# Connector.net
KiCad netlist of a schematic drawn in Altium Designer
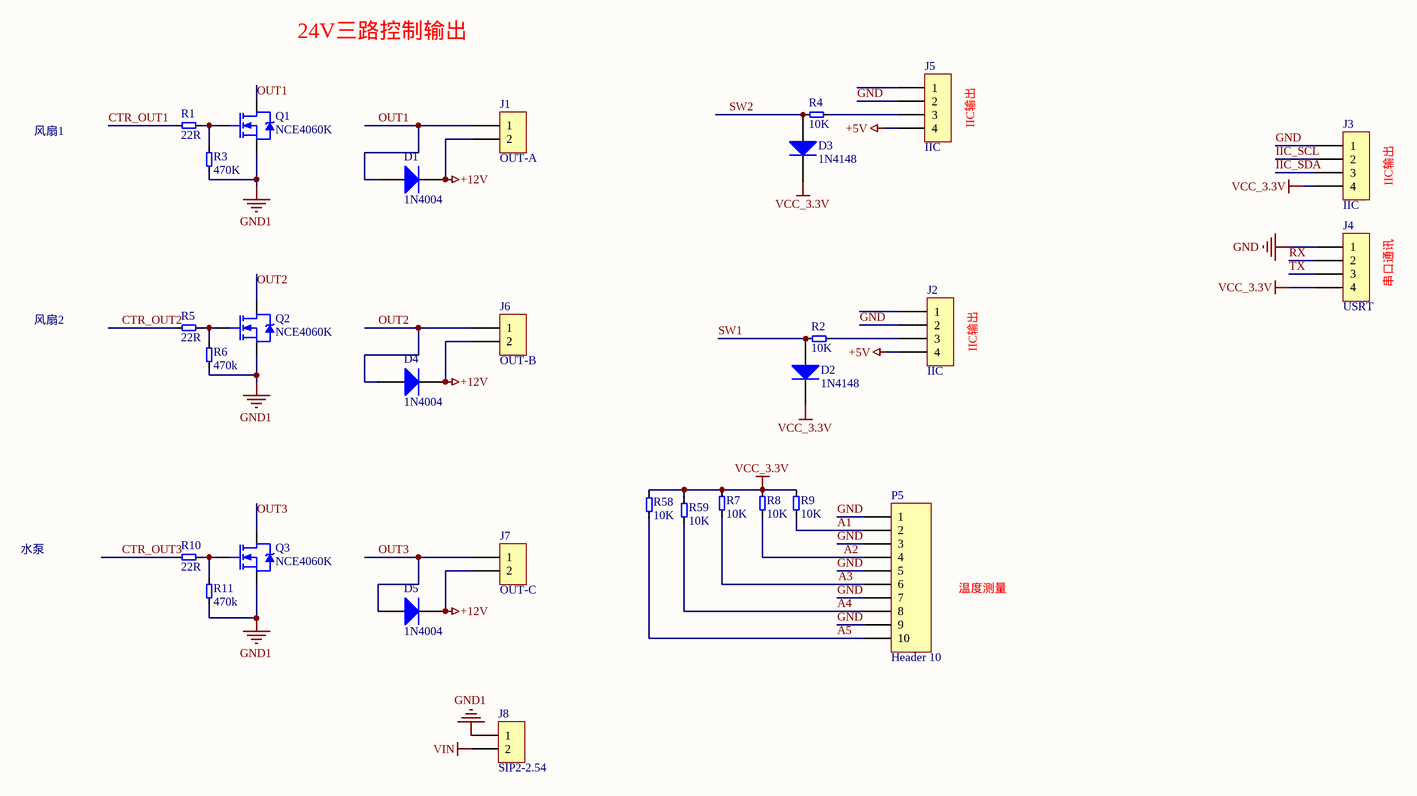
[diagram p0: Connector.SchDoc]

(export (version "E")
  (design (tool "Eeschema 10.0.6"))
  (components
    (comp (ref "D1")
      (value "1N4004")
      (footprint "D7227")
      (description "Default Diode")
      (fields (field (name "PUBLISHER") "Altium Limited"))
      (libsource (lib "SM") (part "Diode_2"))
    )
    (comp (ref "D2")
      (value "1N4148")
      (footprint "sod323")
      (description "Default Diode")
      (fields (field (name "PUBLISHER") "Altium Limited"))
      (libsource (lib "Miscellaneous Devices") (part "Diode"))
    )
    (comp (ref "D3")
      (value "1N4148")
      (footprint "sod323")
      (description "Default Diode")
      (fields (field (name "PUBLISHER") "Altium Limited"))
      (libsource (lib "Miscellaneous Devices") (part "Diode"))
    )
    (comp (ref "D4")
      (value "1N4004")
      (footprint "D7227")
      (description "Default Diode")
      (fields (field (name "PUBLISHER") "Altium Limited"))
      (libsource (lib "SM") (part "Diode_2"))
    )
    (comp (ref "D5")
      (value "1N4004")
      (footprint "D7227")
      (description "Default Diode")
      (fields (field (name "PUBLISHER") "Altium Limited"))
      (libsource (lib "SM") (part "Diode_2"))
    )
    (comp (ref "J1")
      (value "OUT-A")
      (footprint "CH3.96-2P")
      (description "Connector")
      (libsource (lib "SM") (part "CON2"))
    )
    (comp (ref "J2")
      (value "IIC")
      (footprint "SIP-4L")
      (description "CN-SIP4-2.54")
      (libsource (lib "接插件") (part "SIP4-2.54"))
    )
    (comp (ref "J3")
      (value "IIC")
      (footprint "SIP-4L")
      (description "CN-SIP4-2.54")
      (libsource (lib "接插件") (part "SIP4-2.54"))
    )
    (comp (ref "J4")
      (value "USRT")
      (footprint "SIP-4L")
      (description "CN-SIP4-2.54")
      (libsource (lib "接插件") (part "SIP4-2.54"))
    )
    (comp (ref "J5")
      (value "IIC")
      (footprint "SIP-4L")
      (description "CN-SIP4-2.54")
      (libsource (lib "接插件") (part "SIP4-2.54"))
    )
    (comp (ref "J6")
      (value "OUT-B")
      (footprint "CH3.96-2P")
      (description "Connector")
      (libsource (lib "SM") (part "CON2"))
    )
    (comp (ref "J7")
      (value "OUT-C")
      (footprint "CH3.96-2P")
      (description "Connector")
      (libsource (lib "SM") (part "CON2"))
    )
    (comp (ref "J8")
      (value "SIP2-2.54")
      (footprint "CH3.96-2P")
      (description "CN-SIP2-2.54")
      (libsource (lib "接插件") (part "SIP2-2.54"))
    )
    (comp (ref "P5")
      (value "Header 10")
      (footprint "SIP-10L")
      (description "Header, 10-Pin")
      (fields (field (name "PUBLISHER") "Altium Limited"))
      (libsource (lib "Miscellaneous Connectors") (part "Header 10"))
    )
    (comp (ref "Q1")
      (value "NCE4060K")
      (footprint "TO-252-3S")
      (description "NMOSFET")
      (libsource (lib "SM") (part "NCE4060K"))
    )
    (comp (ref "Q2")
      (value "NCE4060K")
      (footprint "TO-252-3S")
      (description "NMOSFET")
      (libsource (lib "SM") (part "NCE4060K"))
    )
    (comp (ref "Q3")
      (value "NCE4060K")
      (footprint "TO-252-3S")
      (description "NMOSFET")
      (libsource (lib "SM") (part "NCE4060K"))
    )
    (comp (ref "R1")
      (value "22R")
      (footprint "0805R")
      (description "CR85-102J")
      (libsource (lib "SMD电阻") (part "1K"))
    )
    (comp (ref "R2")
      (value "10K")
      (footprint "0805R")
      (description "CR85-102J")
      (libsource (lib "SMD电阻") (part "1K"))
    )
    (comp (ref "R3")
      (value "470K")
      (footprint "0805R")
      (description "CR85-102J")
      (libsource (lib "SMD电阻") (part "1K"))
    )
    (comp (ref "R4")
      (value "10K")
      (footprint "0805R")
      (description "CR85-102J")
      (libsource (lib "SMD电阻") (part "1K"))
    )
    (comp (ref "R5")
      (value "22R")
      (footprint "0805R")
      (description "CR85-102J")
      (libsource (lib "SMD电阻") (part "1K"))
    )
    (comp (ref "R6")
      (value "470k")
      (footprint "0805R")
      (description "CR85-102J")
      (libsource (lib "SMD电阻") (part "1K"))
    )
    (comp (ref "R7")
      (value "10K")
      (footprint "0805R")
      (description "CR85-102J")
      (libsource (lib "SMD电阻") (part "1K"))
    )
    (comp (ref "R8")
      (value "10K")
      (footprint "0805R")
      (description "CR85-102J")
      (libsource (lib "SMD电阻") (part "1K"))
    )
    (comp (ref "R9")
      (value "10K")
      (footprint "0805R")
      (description "CR85-102J")
      (libsource (lib "SMD电阻") (part "1K"))
    )
    (comp (ref "R10")
      (value "22R")
      (footprint "0805R")
      (description "CR85-102J")
      (libsource (lib "SMD电阻") (part "1K"))
    )
    (comp (ref "R11")
      (value "470k")
      (footprint "0805R")
      (description "CR85-102J")
      (libsource (lib "SMD电阻") (part "1K"))
    )
    (comp (ref "R58")
      (value "10K")
      (footprint "0805R")
      (description "CR85-102J")
      (libsource (lib "SMD电阻") (part "1K"))
    )
    (comp (ref "R59")
      (value "10K")
      (footprint "0805R")
      (description "CR85-102J")
      (libsource (lib "SMD电阻") (part "1K"))
    )
  )
  (nets
    (net (code "1") (name "+5V") (class "Default")
      (node (ref "J2") (pin "4") (pinfunction "4_4") (pintype "passive"))
      (node (ref "J5") (pin "4") (pinfunction "4_4") (pintype "passive"))
    )
    (net (code "2") (name "+12V") (class "Default")
      (node (ref "D1") (pin "K") (pinfunction "K_K") (pintype "passive"))
      (node (ref "D4") (pin "K") (pinfunction "K_K") (pintype "passive"))
      (node (ref "D5") (pin "K") (pinfunction "K_K") (pintype "passive"))
      (node (ref "J1") (pin "2") (pinfunction "2_2") (pintype "passive"))
      (node (ref "J6") (pin "2") (pinfunction "2_2") (pintype "passive"))
      (node (ref "J7") (pin "2") (pinfunction "2_2") (pintype "passive"))
    )
    (net (code "3") (name "/A1") (class "Default")
      (node (ref "P5") (pin "2") (pinfunction "2_2") (pintype "passive"))
      (node (ref "R9") (pin "1") (pinfunction "1_1") (pintype "passive"))
    )
    (net (code "4") (name "/A2") (class "Default")
      (node (ref "P5") (pin "4") (pinfunction "4_4") (pintype "passive"))
      (node (ref "R8") (pin "1") (pinfunction "1_1") (pintype "passive"))
    )
    (net (code "5") (name "/A3") (class "Default")
      (node (ref "P5") (pin "6") (pinfunction "6_6") (pintype "passive"))
      (node (ref "R7") (pin "1") (pinfunction "1_1") (pintype "passive"))
    )
    (net (code "6") (name "/A4") (class "Default")
      (node (ref "P5") (pin "8") (pinfunction "8_8") (pintype "passive"))
      (node (ref "R59") (pin "2") (pinfunction "2_2") (pintype "passive"))
    )
    (net (code "7") (name "/A5") (class "Default")
      (node (ref "P5") (pin "10") (pinfunction "10_10") (pintype "passive"))
      (node (ref "R58") (pin "1") (pinfunction "1_1") (pintype "passive"))
    )
    (net (code "8") (name "/CTR_OUT1") (class "Default")
      (node (ref "R1") (pin "1") (pinfunction "1_1") (pintype "passive"))
    )
    (net (code "9") (name "/CTR_OUT2") (class "Default")
      (node (ref "R5") (pin "1") (pinfunction "1_1") (pintype "passive"))
    )
    (net (code "10") (name "/CTR_OUT3") (class "Default")
      (node (ref "R10") (pin "1") (pinfunction "1_1") (pintype "passive"))
    )
    (net (code "11") (name "/IIC_SCL") (class "Default")
      (node (ref "J3") (pin "2") (pinfunction "2_2") (pintype "passive"))
    )
    (net (code "12") (name "/IIC_SDA") (class "Default")
      (node (ref "J3") (pin "3") (pinfunction "3_3") (pintype "passive"))
    )
    (net (code "13") (name "/OUT1") (class "Default")
      (node (ref "D1") (pin "A") (pinfunction "A_A") (pintype "passive"))
      (node (ref "J1") (pin "1") (pinfunction "1_1") (pintype "passive"))
      (node (ref "Q1") (pin "2") (pinfunction "D_2") (pintype "passive"))
    )
    (net (code "14") (name "/OUT2") (class "Default")
      (node (ref "D4") (pin "A") (pinfunction "A_A") (pintype "passive"))
      (node (ref "J6") (pin "1") (pinfunction "1_1") (pintype "passive"))
      (node (ref "Q2") (pin "2") (pinfunction "D_2") (pintype "passive"))
    )
    (net (code "15") (name "/OUT3") (class "Default")
      (node (ref "D5") (pin "A") (pinfunction "A_A") (pintype "passive"))
      (node (ref "J7") (pin "1") (pinfunction "1_1") (pintype "passive"))
      (node (ref "Q3") (pin "2") (pinfunction "D_2") (pintype "passive"))
    )
    (net (code "16") (name "/RX") (class "Default")
      (node (ref "J4") (pin "2") (pinfunction "2_2") (pintype "passive"))
    )
    (net (code "17") (name "/SW1") (class "Default")
      (node (ref "D2") (pin "A") (pinfunction "A_A") (pintype "passive"))
      (node (ref "R2") (pin "2") (pinfunction "2_2") (pintype "passive"))
    )
    (net (code "18") (name "/SW2") (class "Default")
      (node (ref "D3") (pin "A") (pinfunction "A_A") (pintype "passive"))
      (node (ref "R4") (pin "2") (pinfunction "2_2") (pintype "passive"))
    )
    (net (code "19") (name "/TX") (class "Default")
      (node (ref "J4") (pin "3") (pinfunction "3_3") (pintype "passive"))
    )
    (net (code "20") (name "GND") (class "Default")
      (node (ref "J2") (pin "2") (pinfunction "2_2") (pintype "passive"))
      (node (ref "J3") (pin "1") (pinfunction "1_1") (pintype "passive"))
      (node (ref "J4") (pin "1") (pinfunction "1_1") (pintype "passive"))
      (node (ref "J5") (pin "2") (pinfunction "2_2") (pintype "passive"))
      (node (ref "P5") (pin "1") (pinfunction "1_1") (pintype "passive"))
      (node (ref "P5") (pin "3") (pinfunction "3_3") (pintype "passive"))
      (node (ref "P5") (pin "5") (pinfunction "5_5") (pintype "passive"))
      (node (ref "P5") (pin "7") (pinfunction "7_7") (pintype "passive"))
      (node (ref "P5") (pin "9") (pinfunction "9_9") (pintype "passive"))
    )
    (net (code "21") (name "GND1") (class "Default")
      (node (ref "J8") (pin "1") (pinfunction "1_1") (pintype "passive"))
      (node (ref "Q1") (pin "3") (pinfunction "S_3") (pintype "passive"))
      (node (ref "Q2") (pin "3") (pinfunction "S_3") (pintype "passive"))
      (node (ref "Q3") (pin "3") (pinfunction "S_3") (pintype "passive"))
      (node (ref "R11") (pin "1") (pinfunction "1_1") (pintype "passive"))
      (node (ref "R3") (pin "1") (pinfunction "1_1") (pintype "passive"))
      (node (ref "R6") (pin "1") (pinfunction "1_1") (pintype "passive"))
    )
    (net (code "22") (name "Net-(J2-Pad3)") (class "Default")
      (node (ref "J2") (pin "3") (pinfunction "3_3") (pintype "passive"))
      (node (ref "R2") (pin "1") (pinfunction "1_1") (pintype "passive"))
    )
    (net (code "23") (name "Net-(J5-Pad3)") (class "Default")
      (node (ref "J5") (pin "3") (pinfunction "3_3") (pintype "passive"))
      (node (ref "R4") (pin "1") (pinfunction "1_1") (pintype "passive"))
    )
    (net (code "24") (name "Net-(Q1-G)") (class "Default")
      (node (ref "Q1") (pin "1") (pinfunction "G_1") (pintype "passive"))
      (node (ref "R1") (pin "2") (pinfunction "2_2") (pintype "passive"))
      (node (ref "R3") (pin "2") (pinfunction "2_2") (pintype "passive"))
    )
    (net (code "25") (name "Net-(Q2-G)") (class "Default")
      (node (ref "Q2") (pin "1") (pinfunction "G_1") (pintype "passive"))
      (node (ref "R5") (pin "2") (pinfunction "2_2") (pintype "passive"))
      (node (ref "R6") (pin "2") (pinfunction "2_2") (pintype "passive"))
    )
    (net (code "26") (name "Net-(Q3-G)") (class "Default")
      (node (ref "Q3") (pin "1") (pinfunction "G_1") (pintype "passive"))
      (node (ref "R10") (pin "2") (pinfunction "2_2") (pintype "passive"))
      (node (ref "R11") (pin "2") (pinfunction "2_2") (pintype "passive"))
    )
    (net (code "27") (name "VCC_3.3V") (class "Default")
      (node (ref "D2") (pin "K") (pinfunction "K_K") (pintype "passive"))
      (node (ref "D3") (pin "K") (pinfunction "K_K") (pintype "passive"))
      (node (ref "J3") (pin "4") (pinfunction "4_4") (pintype "passive"))
      (node (ref "J4") (pin "4") (pinfunction "4_4") (pintype "passive"))
      (node (ref "R58") (pin "2") (pinfunction "2_2") (pintype "passive"))
      (node (ref "R59") (pin "1") (pinfunction "1_1") (pintype "passive"))
      (node (ref "R7") (pin "2") (pinfunction "2_2") (pintype "passive"))
      (node (ref "R8") (pin "2") (pinfunction "2_2") (pintype "passive"))
      (node (ref "R9") (pin "2") (pinfunction "2_2") (pintype "passive"))
    )
    (net (code "28") (name "VIN") (class "Default")
      (node (ref "J8") (pin "2") (pinfunction "2_2") (pintype "passive"))
    )
    (net (code "29") (name "unconnected-(J2-Pad1)") (class "Default")
      (node (ref "J2") (pin "1") (pinfunction "1_1") (pintype "passive"))
    )
    (net (code "30") (name "unconnected-(J5-Pad1)") (class "Default")
      (node (ref "J5") (pin "1") (pinfunction "1_1") (pintype "passive"))
    )
  )
)
